# IMU.net
KiCad netlist of a schematic drawn in Altium Designer
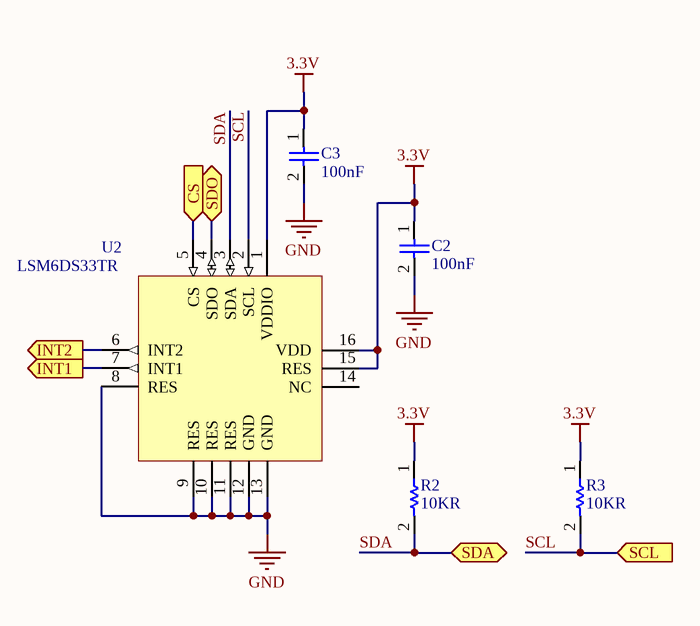
[diagram p0: IMU.SchDoc]

(export (version "E")
  (design (tool "Eeschema 10.0.6"))
  (components
    (comp (ref "C2")
      (value "100nF")
      (footprint "MURA-0603_H_0.9_N")
      (description "X7R,.1UF,20%,16V,UNMARKED, 1.0A 40V ROHS 3K<AZ")
      (fields
        (field (name "MANUFACTURER") "KEMET")
        (field (name "MANUFACTURER PART NUMBER") "C0603C104M4RAC7411")
      )
      (libsource (lib "IMU") (part "C0603C104M4RAC7411"))
    )
    (comp (ref "C3")
      (value "100nF")
      (footprint "MURA-0603_H_0.9_N")
      (description "X7R,.1UF,20%,16V,UNMARKED, 1.0A 40V ROHS 3K<AZ")
      (fields
        (field (name "MANUFACTURER") "KEMET")
        (field (name "MANUFACTURER PART NUMBER") "C0603C104M4RAC7411")
      )
      (libsource (lib "IMU") (part "C0603C104M4RAC7411"))
    )
    (comp (ref "R2")
      (value "10KR")
      (footprint "RESC1609X50X30NL8T20")
      (fields
        (field (name "MANUFACTURER") "Vishay")
        (field (name "MANUFACTURER PART NUMBER") "CRCW060310K0FKEA")
        (field (name "TOLERANCE") "1%")
      )
      (libsource (lib "IMU") (part "CRCW060310K0FKEA"))
    )
    (comp (ref "R3")
      (value "10KR")
      (footprint "RESC1609X50X30NL8T20")
      (fields
        (field (name "MANUFACTURER") "Vishay")
        (field (name "MANUFACTURER PART NUMBER") "CRCW060310K0FKEA")
        (field (name "TOLERANCE") "1%")
      )
      (libsource (lib "IMU") (part "CRCW060310K0FKEA"))
    )
    (comp (ref "U2")
      (value "LSM6DS33TR")
      (footprint "*PQFN50P300X300X86-16N")
      (description "MOTION MEMS CONSUMER")
      (fields (field (name "MANUFACTURER") "STMicroelectronics"))
      (libsource (lib "IMU") (part "LSM6DS33TR"))
    )
  )
  (nets
    (net (code "1") (name "/CS") (class "Default")
      (node (ref "U2") (pin "5") (pinfunction "CS_5") (pintype "input"))
    )
    (net (code "2") (name "/INT1") (class "Default")
      (node (ref "U2") (pin "7") (pinfunction "INT1_7") (pintype "output"))
    )
    (net (code "3") (name "/INT2") (class "Default")
      (node (ref "U2") (pin "6") (pinfunction "INT2_6") (pintype "output"))
    )
    (net (code "4") (name "/SCL") (class "Default")
      (node (ref "R3") (pin "2") (pinfunction "2_2") (pintype "passive"))
      (node (ref "U2") (pin "2") (pinfunction "SCL_2") (pintype "input"))
    )
    (net (code "5") (name "/SDA") (class "Default")
      (node (ref "R2") (pin "2") (pinfunction "2_2") (pintype "passive"))
      (node (ref "U2") (pin "3") (pinfunction "SDA_3") (pintype "bidirectional"))
    )
    (net (code "6") (name "/SDO") (class "Default")
      (node (ref "U2") (pin "4") (pinfunction "SDO_4") (pintype "bidirectional"))
    )
    (net (code "7") (name "3.3V") (class "Default")
      (node (ref "C2") (pin "1") (pinfunction "1_1") (pintype "passive"))
      (node (ref "C3") (pin "1") (pinfunction "1_1") (pintype "passive"))
      (node (ref "R2") (pin "1") (pinfunction "1_1") (pintype "passive"))
      (node (ref "R3") (pin "1") (pinfunction "1_1") (pintype "passive"))
      (node (ref "U2") (pin "1") (pinfunction "VDDIO_1") (pintype "power_in"))
      (node (ref "U2") (pin "15") (pinfunction "RES_15") (pintype "passive"))
      (node (ref "U2") (pin "16") (pinfunction "VDD_16") (pintype "power_in"))
    )
    (net (code "8") (name "GND") (class "Default")
      (node (ref "C2") (pin "2") (pinfunction "2_2") (pintype "passive"))
      (node (ref "C3") (pin "2") (pinfunction "2_2") (pintype "passive"))
      (node (ref "U2") (pin "10") (pinfunction "RES_10") (pintype "passive"))
      (node (ref "U2") (pin "11") (pinfunction "RES_11") (pintype "passive"))
      (node (ref "U2") (pin "12") (pinfunction "GND_12") (pintype "power_in"))
      (node (ref "U2") (pin "13") (pinfunction "GND_13") (pintype "power_in"))
      (node (ref "U2") (pin "8") (pinfunction "RES_8") (pintype "passive"))
      (node (ref "U2") (pin "9") (pinfunction "RES_9") (pintype "passive"))
    )
    (net (code "9") (name "unconnected-(U2-NC-Pad14)") (class "Default")
      (node (ref "U2") (pin "14") (pinfunction "NC_14") (pintype "passive"))
    )
  )
)
